# Sheet1.net
KiCad netlist of a schematic drawn in Altium Designer
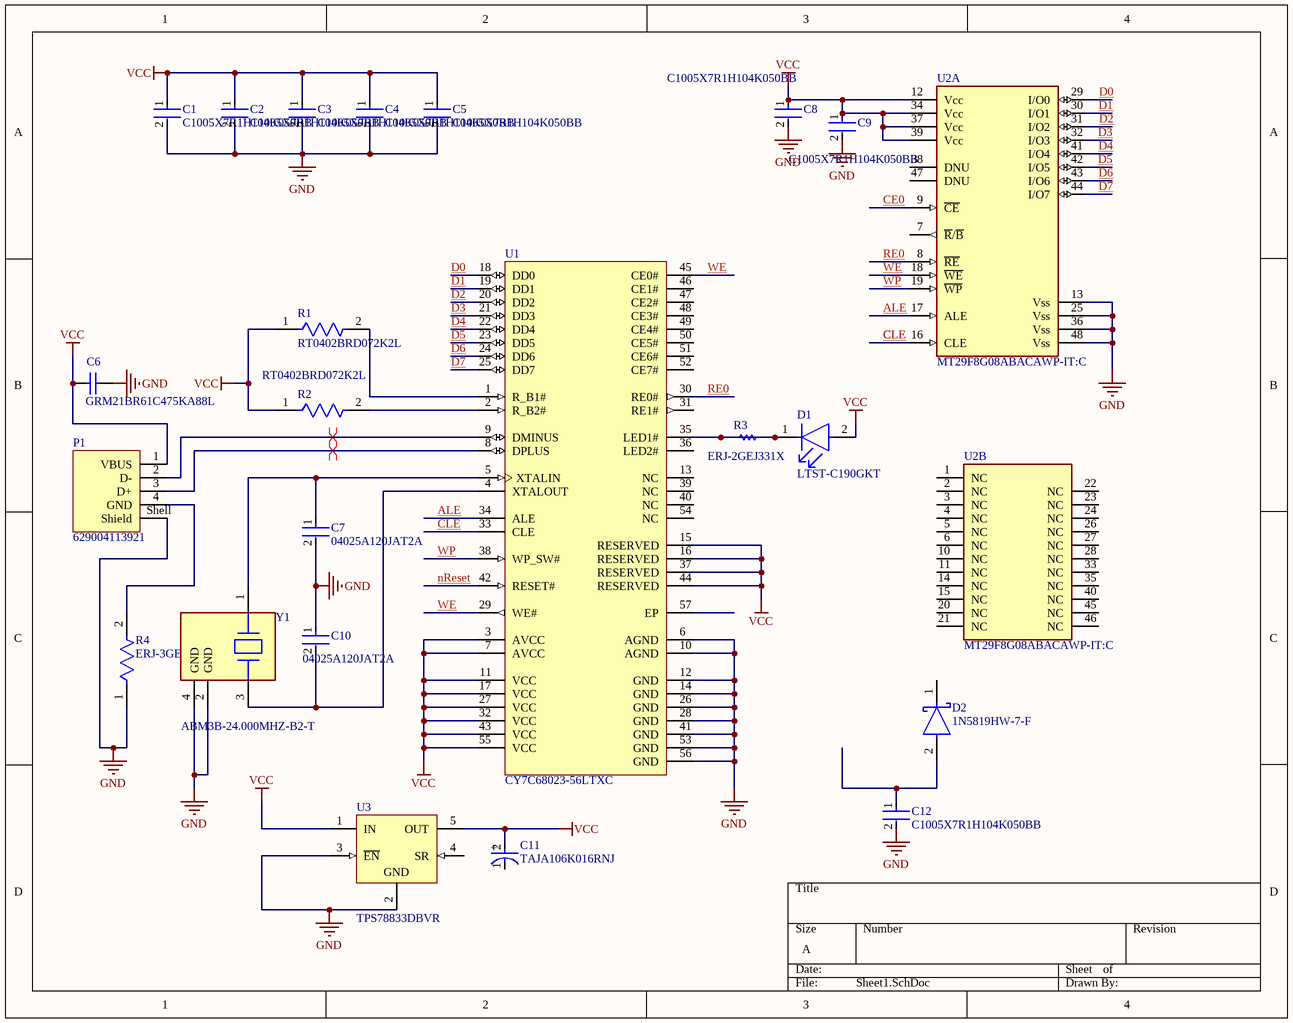
[diagram p0: Sheet1.SchDoc]

(export (version "E")
  (design (tool "Eeschema 10.0.6"))
  (components
    (comp (ref "C1")
      (value "C1005X7R1H104K050BB")
      (footprint "FP-C1005-050-0_05-IPC_C")
      (description "Multilayer Ceramic Capacitors 100nF ±10% 50V X7R SMD 0402")
      (fields (field (name "VOLTAGE") "50V") (field (name "TOLERANCE") "10%"))
      (libsource (lib "Altium Content Vault") (part "b4654b650e69147ec39a6b967a45e02"))
    )
    (comp (ref "C2")
      (value "C1005X7R1H104K050BB")
      (footprint "FP-C1005-050-0_05-IPC_C")
      (description "Multilayer Ceramic Capacitors 100nF ±10% 50V X7R SMD 0402")
      (fields (field (name "VOLTAGE") "50V") (field (name "TOLERANCE") "10%"))
      (libsource (lib "Altium Content Vault") (part "b4654b650e69147ec39a6b967a45e02"))
    )
    (comp (ref "C3")
      (value "C1005X7R1H104K050BB")
      (footprint "FP-C1005-050-0_05-IPC_C")
      (description "Multilayer Ceramic Capacitors 100nF ±10% 50V X7R SMD 0402")
      (fields (field (name "VOLTAGE") "50V") (field (name "TOLERANCE") "10%"))
      (libsource (lib "Altium Content Vault") (part "b4654b650e69147ec39a6b967a45e02"))
    )
    (comp (ref "C4")
      (value "C1005X7R1H104K050BB")
      (footprint "FP-C1005-050-0_05-IPC_C")
      (description "Multilayer Ceramic Capacitors 100nF ±10% 50V X7R SMD 0402")
      (fields (field (name "VOLTAGE") "50V") (field (name "TOLERANCE") "10%"))
      (libsource (lib "Altium Content Vault") (part "b4654b650e69147ec39a6b967a45e02"))
    )
    (comp (ref "C5")
      (value "C1005X7R1H104K050BB")
      (footprint "FP-C1005-050-0_05-IPC_C")
      (description "Multilayer Ceramic Capacitors 100nF ±10% 50V X7R SMD 0402")
      (fields (field (name "VOLTAGE") "50V") (field (name "TOLERANCE") "10%"))
      (libsource (lib "Altium Content Vault") (part "b4654b650e69147ec39a6b967a45e02"))
    )
    (comp (ref "C6")
      (value "GRM21BR61C475KA88L")
      (footprint "CAPC2013X135X45LL10T25")
      (description "Chip Capacitor, 4.7 uF, +/- 10%, 16 V, -55 to 85 degC, 0805 (2012 Metric), RoHS, Tape and Reel")
      (fields (field (name "TOLERANCE") "10%"))
      (libsource (lib "Altium Content Vault") (part "CAP-NP-2"))
    )
    (comp (ref "C7")
      (value "04025A120JAT2A")
      (footprint "FP-0402-L_1_0_1-W_0_5_0_1-IPC_B")
      (description "General Purpose Ceramic Capacitor, 0402, 12pF, 5%, C0G, 30ppm/°C, 50V")
      (fields (field (name "VOLTAGE") "50V") (field (name "TOLERANCE") "5%"))
      (libsource (lib "Altium Content Vault") (part "b4654b650e69147ec39a6b967a45e02"))
    )
    (comp (ref "C8")
      (value "C1005X7R1H104K050BB")
      (footprint "FP-C1005-050-0_05-IPC_C")
      (description "Multilayer Ceramic Capacitors 100nF ±10% 50V X7R SMD 0402")
      (fields (field (name "VOLTAGE") "50V") (field (name "TOLERANCE") "10%"))
      (libsource (lib "Altium Content Vault") (part "b4654b650e69147ec39a6b967a45e02"))
    )
    (comp (ref "C9")
      (value "C1005X7R1H104K050BB")
      (footprint "FP-C1005-050-0_05-IPC_C")
      (description "Multilayer Ceramic Capacitors 100nF ±10% 50V X7R SMD 0402")
      (fields (field (name "VOLTAGE") "50V") (field (name "TOLERANCE") "10%"))
      (libsource (lib "Altium Content Vault") (part "b4654b650e69147ec39a6b967a45e02"))
    )
    (comp (ref "C10")
      (value "04025A120JAT2A")
      (footprint "FP-0402-L_1_0_1-W_0_5_0_1-IPC_B")
      (description "General Purpose Ceramic Capacitor, 0402, 12pF, 5%, C0G, 30ppm/°C, 50V")
      (fields (field (name "VOLTAGE") "50V") (field (name "TOLERANCE") "5%"))
      (libsource (lib "Altium Content Vault") (part "b4654b650e69147ec39a6b967a45e02"))
    )
    (comp (ref "C11")
      (value "TAJA106K016RNJ")
      (footprint "FP-TAJA-MFG")
      (description "10uF 16V  ±10% 3Ω 1206  SMD Tantalum Capacitor")
      (fields (field (name "VOLTAGE") "16V") (field (name "TOLERANCE") "10%"))
      (libsource (lib "Altium Content Vault") (part "203bc49f2ac43e59fd269a8c329ed05"))
    )
    (comp (ref "C12")
      (value "C1005X7R1H104K050BB")
      (footprint "FP-C1005-050-0_05-IPC_C")
      (description "Multilayer Ceramic Capacitors 100nF ±10% 50V X7R SMD 0402")
      (fields (field (name "VOLTAGE") "50V") (field (name "TOLERANCE") "10%"))
      (libsource (lib "Altium Content Vault") (part "b4654b650e69147ec39a6b967a45e02"))
    )
    (comp (ref "D1")
      (value "LTST-C190GKT")
      (footprint "FP-LTST-C190GKT-MFG")
      (description "LED GREEN CLEAR CHIP SMD")
      (fields (field (name "VOLTAGE") "2V"))
      (libsource (lib "Altium Content Vault") (part "8706943c75ba83719d021d2fdc84c58"))
    )
    (comp (ref "D2")
      (value "1N5819HW-7-F")
      (footprint "FP-SOD123-IPC_A")
      (description "DIODE SCHOTTKY 40V 1A SOD123")
      (libsource (lib "Altium Content Vault") (part "1d6ec82d83fb6aee721767c19dac4b9"))
    )
    (comp (ref "P1")
      (value "629004113921")
      (footprint "629004113921")
      (libsource (lib "Altium Content Vault") (part "USB 2.0_Type A_Plug_1 Port"))
    )
    (comp (ref "R1")
      (value "RT0402BRD072K2L")
      (footprint "FP-RT0402-MFG")
      (description "RES SMD 2.2K OHM 0.1% 1/16W 0402")
      (fields (field (name "MANUFACTURER") "Yageo") (field (name "TOLERANCE") "0.001"))
      (libsource (lib "Altium Content Vault") (part "1029c3af85768c4190bb7ad29bc67b5"))
    )
    (comp (ref "R2")
      (value "RT0402BRD072K2L")
      (footprint "FP-RT0402-MFG")
      (description "RES SMD 2.2K OHM 0.1% 1/16W 0402")
      (fields (field (name "MANUFACTURER") "Yageo") (field (name "TOLERANCE") "0.001"))
      (libsource (lib "Altium Content Vault") (part "1029c3af85768c4190bb7ad29bc67b5"))
    )
    (comp (ref "R3")
      (value "ERJ-2GEJ331X")
      (footprint "RESC1005X40X25NL05T05")
      (fields (field (name "MANUFACTURER") "Panasonic"))
      (libsource (lib "Altium Content Vault") (part "RES"))
    )
    (comp (ref "R4")
      (value "ERJ-3GEY0R00V")
      (footprint "FP-ERJ-3GEY0R00V-MFG")
      (description "RES SMD 0 OHM JUMPER 1/10W 0603")
      (fields (field (name "TOLERANCE") "5%") (field (name "MANUFACTURER") "Panasonic"))
      (libsource (lib "Altium Content Vault") (part "1029c3af85768c4190bb7ad29bc67b5"))
    )
    (comp (ref "U1")
      (value "CY7C68023-56LTXC")
      (footprint "CYP-LTX56-5200X4500TP_M")
      (fields (field (name "MANUFACTURER") "Cypress"))
      (libsource (lib "Altium Content Vault") (part "CYP-CY7C68023-LTX56"))
    )
    (comp (ref "U2")
      (value "MT29F8G08ABACAWP-IT:C")
      (footprint "FP-WP-IPC_C")
      (description "IC FLASH 8GBIT PARALLEL 48TSOP I")
      (libsource (lib "Altium Content Vault") (part "ae830fc3658e7ec601516aea8518371"))
    )
    (comp (ref "U3")
      (value "TPS78833DBVR")
      (footprint "DBV0005A_M")
      (fields (field (name "MANUFACTURER") "Texas Instruments"))
      (libsource (lib "Altium Content Vault") (part "TI-TPS788XXDBV5"))
    )
    (comp (ref "Y1")
      (value "ABM3B-24.000MHZ-B2-T")
      (footprint "FP-ABM3B-MFG")
      (description "Crystal 24MHz ±20ppm 18pF SMD-4 5mm x 3.2mm")
      (fields (field (name "TOLERANCE") "20ppm"))
      (libsource (lib "Altium Content Vault") (part "48e526d86b7f2615d98721063c72f49"))
    )
  )
  (nets
    (net (code "1") (name "/ALE") (class "Default")
      (node (ref "U1") (pin "34") (pinfunction "ALE_34") (pintype "tri_state"))
      (node (ref "U2") (pin "17") (pinfunction "ALE_17") (pintype "input"))
    )
    (net (code "2") (name "/CE0") (class "Default")
      (node (ref "U2") (pin "9") (pinfunction "~{CE}_9") (pintype "input"))
    )
    (net (code "3") (name "/CLE") (class "Default")
      (node (ref "U1") (pin "33") (pinfunction "CLE_33") (pintype "tri_state"))
      (node (ref "U2") (pin "16") (pinfunction "CLE_16") (pintype "input"))
    )
    (net (code "4") (name "/D0") (class "Default")
      (node (ref "U1") (pin "18") (pinfunction "DD0_18") (pintype "bidirectional"))
      (node (ref "U2") (pin "29") (pinfunction "I/O0_29") (pintype "bidirectional"))
    )
    (net (code "5") (name "/D1") (class "Default")
      (node (ref "U1") (pin "19") (pinfunction "DD1_19") (pintype "bidirectional"))
      (node (ref "U2") (pin "30") (pinfunction "I/O1_30") (pintype "bidirectional"))
    )
    (net (code "6") (name "/D2") (class "Default")
      (node (ref "U1") (pin "20") (pinfunction "DD2_20") (pintype "bidirectional"))
      (node (ref "U2") (pin "31") (pinfunction "I/O2_31") (pintype "bidirectional"))
    )
    (net (code "7") (name "/D3") (class "Default")
      (node (ref "U1") (pin "21") (pinfunction "DD3_21") (pintype "bidirectional"))
      (node (ref "U2") (pin "32") (pinfunction "I/O3_32") (pintype "bidirectional"))
    )
    (net (code "8") (name "/D4") (class "Default")
      (node (ref "U1") (pin "22") (pinfunction "DD4_22") (pintype "bidirectional"))
      (node (ref "U2") (pin "41") (pinfunction "I/O4_41") (pintype "bidirectional"))
    )
    (net (code "9") (name "/D5") (class "Default")
      (node (ref "U1") (pin "23") (pinfunction "DD5_23") (pintype "bidirectional"))
      (node (ref "U2") (pin "42") (pinfunction "I/O5_42") (pintype "bidirectional"))
    )
    (net (code "10") (name "/D6") (class "Default")
      (node (ref "U1") (pin "24") (pinfunction "DD6_24") (pintype "bidirectional"))
      (node (ref "U2") (pin "43") (pinfunction "I/O6_43") (pintype "bidirectional"))
    )
    (net (code "11") (name "/D7") (class "Default")
      (node (ref "U1") (pin "25") (pinfunction "DD7_25") (pintype "bidirectional"))
      (node (ref "U2") (pin "44") (pinfunction "I/O7_44") (pintype "bidirectional"))
    )
    (net (code "12") (name "/RE0") (class "Default")
      (node (ref "U1") (pin "30") (pinfunction "RE0#_30") (pintype "output"))
      (node (ref "U2") (pin "8") (pinfunction "~{RE}_8") (pintype "input"))
    )
    (net (code "13") (name "/WE") (class "Default")
      (node (ref "U1") (pin "29") (pinfunction "WE#_29") (pintype "output"))
      (node (ref "U1") (pin "45") (pinfunction "CE0#_45") (pintype "tri_state"))
      (node (ref "U2") (pin "18") (pinfunction "~{WE}_18") (pintype "input"))
    )
    (net (code "14") (name "/WP") (class "Default")
      (node (ref "U1") (pin "38") (pinfunction "WP_SW#_38") (pintype "input"))
      (node (ref "U2") (pin "19") (pinfunction "~{WP}_19") (pintype "input"))
    )
    (net (code "15") (name "/nReset") (class "Default")
      (node (ref "U1") (pin "42") (pinfunction "RESET#_42") (pintype "input"))
    )
    (net (code "16") (name "GND") (class "Default")
      (node (ref "C1") (pin "2") (pinfunction "2_2") (pintype "passive"))
      (node (ref "C10") (pin "1") (pinfunction "1_1") (pintype "passive"))
      (node (ref "C12") (pin "2") (pinfunction "2_2") (pintype "passive"))
      (node (ref "C2") (pin "2") (pinfunction "2_2") (pintype "passive"))
      (node (ref "C3") (pin "2") (pinfunction "2_2") (pintype "passive"))
      (node (ref "C4") (pin "2") (pinfunction "2_2") (pintype "passive"))
      (node (ref "C5") (pin "2") (pinfunction "2_2") (pintype "passive"))
      (node (ref "C6") (pin "2") (pinfunction "2_2") (pintype "passive"))
      (node (ref "C7") (pin "2") (pinfunction "2_2") (pintype "passive"))
      (node (ref "C8") (pin "2") (pinfunction "2_2") (pintype "passive"))
      (node (ref "C9") (pin "2") (pinfunction "2_2") (pintype "passive"))
      (node (ref "P1") (pin "Shell") (pinfunction "Shield_Shell") (pintype "passive"))
      (node (ref "R4") (pin "1") (pinfunction "1_1") (pintype "passive"))
      (node (ref "U1") (pin "10") (pinfunction "AGND_10") (pintype "power_in"))
      (node (ref "U1") (pin "12") (pinfunction "GND_12") (pintype "power_in"))
      (node (ref "U1") (pin "14") (pinfunction "GND_14") (pintype "power_in"))
      (node (ref "U1") (pin "26") (pinfunction "GND_26") (pintype "power_in"))
      (node (ref "U1") (pin "28") (pinfunction "GND_28") (pintype "power_in"))
      (node (ref "U1") (pin "41") (pinfunction "GND_41") (pintype "power_in"))
      (node (ref "U1") (pin "53") (pinfunction "GND_53") (pintype "power_in"))
      (node (ref "U1") (pin "56") (pinfunction "GND_56") (pintype "power_in"))
      (node (ref "U1") (pin "6") (pinfunction "AGND_6") (pintype "power_in"))
      (node (ref "U2") (pin "13") (pinfunction "Vss_13") (pintype "power_in"))
      (node (ref "U2") (pin "25") (pinfunction "Vss_25") (pintype "power_in"))
      (node (ref "U2") (pin "36") (pinfunction "Vss_36") (pintype "power_in"))
      (node (ref "U2") (pin "48") (pinfunction "Vss_48") (pintype "power_in"))
      (node (ref "U3") (pin "2") (pinfunction "GND_2") (pintype "power_in"))
      (node (ref "U3") (pin "3") (pinfunction "~{EN}_3") (pintype "input"))
      (node (ref "Y1") (pin "2") (pinfunction "GND_2") (pintype "power_in"))
      (node (ref "Y1") (pin "4") (pinfunction "GND_4") (pintype "power_in"))
    )
    (net (code "17") (name "Net-(D1-C)") (class "Default")
      (node (ref "D1") (pin "1") (pinfunction "C_1") (pintype "passive"))
      (node (ref "R3") (pin "1") (pinfunction "1_1") (pintype "passive"))
      (node (ref "R3") (pin "2") (pinfunction "2_2") (pintype "passive"))
      (node (ref "U1") (pin "35") (pinfunction "LED1#_35") (pintype "tri_state"))
    )
    (net (code "18") (name "Net-(D2-A)") (class "Default")
      (node (ref "C12") (pin "1") (pinfunction "1_1") (pintype "passive"))
      (node (ref "D2") (pin "2") (pinfunction "A_2") (pintype "passive"))
    )
    (net (code "19") (name "Net-(P1-D+)") (class "Default")
      (node (ref "P1") (pin "3") (pinfunction "D+_3") (pintype "passive"))
      (node (ref "U1") (pin "8") (pinfunction "DPLUS_8") (pintype "bidirectional"))
    )
    (net (code "20") (name "Net-(P1-D-)") (class "Default")
      (node (ref "P1") (pin "2") (pinfunction "D-_2") (pintype "passive"))
      (node (ref "U1") (pin "9") (pinfunction "DMINUS_9") (pintype "bidirectional"))
    )
    (net (code "21") (name "Net-(P1-GND)") (class "Default")
      (node (ref "P1") (pin "4") (pinfunction "GND_4") (pintype "passive"))
      (node (ref "R4") (pin "2") (pinfunction "2_2") (pintype "passive"))
    )
    (net (code "22") (name "Net-(U1-R_B1#)") (class "Default")
      (node (ref "R1") (pin "2") (pinfunction "2_2") (pintype "passive"))
      (node (ref "U1") (pin "1") (pinfunction "R_B1#_1") (pintype "input"))
    )
    (net (code "23") (name "Net-(U1-R_B2#)") (class "Default")
      (node (ref "R2") (pin "2") (pinfunction "2_2") (pintype "passive"))
      (node (ref "U1") (pin "2") (pinfunction "R_B2#_2") (pintype "input"))
    )
    (net (code "24") (name "Net-(U1-XTALIN)") (class "Default")
      (node (ref "C7") (pin "1") (pinfunction "1_1") (pintype "passive"))
      (node (ref "U1") (pin "5") (pinfunction "XTALIN_5") (pintype "input"))
      (node (ref "Y1") (pin "1") (pinfunction "1_1") (pintype "passive"))
    )
    (net (code "25") (name "Net-(U1-XTALOUT)") (class "Default")
      (node (ref "C10") (pin "2") (pinfunction "2_2") (pintype "passive"))
      (node (ref "U1") (pin "4") (pinfunction "XTALOUT_4") (pintype "passive"))
      (node (ref "Y1") (pin "3") (pinfunction "3_3") (pintype "passive"))
    )
    (net (code "26") (name "VCC") (class "Default")
      (node (ref "C1") (pin "1") (pinfunction "1_1") (pintype "passive"))
      (node (ref "C11") (pin "2") (pinfunction "A_2") (pintype "passive"))
      (node (ref "C2") (pin "1") (pinfunction "1_1") (pintype "passive"))
      (node (ref "C3") (pin "1") (pinfunction "1_1") (pintype "passive"))
      (node (ref "C4") (pin "1") (pinfunction "1_1") (pintype "passive"))
      (node (ref "C5") (pin "1") (pinfunction "1_1") (pintype "passive"))
      (node (ref "C6") (pin "1") (pinfunction "1_1") (pintype "passive"))
      (node (ref "C8") (pin "1") (pinfunction "1_1") (pintype "passive"))
      (node (ref "C9") (pin "1") (pinfunction "1_1") (pintype "passive"))
      (node (ref "D1") (pin "2") (pinfunction "A_2") (pintype "passive"))
      (node (ref "P1") (pin "1") (pinfunction "VBUS_1") (pintype "passive"))
      (node (ref "R1") (pin "1") (pinfunction "1_1") (pintype "passive"))
      (node (ref "R2") (pin "1") (pinfunction "1_1") (pintype "passive"))
      (node (ref "U1") (pin "11") (pinfunction "VCC_11") (pintype "power_in"))
      (node (ref "U1") (pin "15") (pinfunction "RESERVED_15") (pintype "passive"))
      (node (ref "U1") (pin "16") (pinfunction "RESERVED_16") (pintype "passive"))
      (node (ref "U1") (pin "17") (pinfunction "VCC_17") (pintype "power_in"))
      (node (ref "U1") (pin "27") (pinfunction "VCC_27") (pintype "power_in"))
      (node (ref "U1") (pin "3") (pinfunction "AVCC_3") (pintype "power_in"))
      (node (ref "U1") (pin "32") (pinfunction "VCC_32") (pintype "power_in"))
      (node (ref "U1") (pin "37") (pinfunction "RESERVED_37") (pintype "passive"))
      (node (ref "U1") (pin "43") (pinfunction "VCC_43") (pintype "power_in"))
      (node (ref "U1") (pin "44") (pinfunction "RESERVED_44") (pintype "passive"))
      (node (ref "U1") (pin "55") (pinfunction "VCC_55") (pintype "power_in"))
      (node (ref "U1") (pin "7") (pinfunction "AVCC_7") (pintype "power_in"))
      (node (ref "U2") (pin "12") (pinfunction "Vcc_12") (pintype "power_in"))
      (node (ref "U2") (pin "34") (pinfunction "Vcc_34") (pintype "power_in"))
      (node (ref "U2") (pin "37") (pinfunction "Vcc_37") (pintype "passive"))
      (node (ref "U2") (pin "39") (pinfunction "Vcc_39") (pintype "power_in"))
      (node (ref "U3") (pin "1") (pinfunction "IN_1") (pintype "power_in"))
      (node (ref "U3") (pin "5") (pinfunction "OUT_5") (pintype "power_in"))
    )
    (net (code "27") (name "unconnected-(C11-C-Pad1)") (class "Default")
      (node (ref "C11") (pin "1") (pinfunction "C_1") (pintype "passive"))
    )
    (net (code "28") (name "unconnected-(D2-C-Pad1)") (class "Default")
      (node (ref "D2") (pin "1") (pinfunction "C_1") (pintype "passive"))
    )
    (net (code "29") (name "unconnected-(U1-CE1#-Pad46)") (class "Default")
      (node (ref "U1") (pin "46") (pinfunction "CE1#_46") (pintype "tri_state"))
    )
    (net (code "30") (name "unconnected-(U1-CE2#-Pad47)") (class "Default")
      (node (ref "U1") (pin "47") (pinfunction "CE2#_47") (pintype "tri_state"))
    )
    (net (code "31") (name "unconnected-(U1-CE3#-Pad48)") (class "Default")
      (node (ref "U1") (pin "48") (pinfunction "CE3#_48") (pintype "tri_state"))
    )
    (net (code "32") (name "unconnected-(U1-CE4#-Pad49)") (class "Default")
      (node (ref "U1") (pin "49") (pinfunction "CE4#_49") (pintype "tri_state"))
    )
    (net (code "33") (name "unconnected-(U1-CE5#-Pad50)") (class "Default")
      (node (ref "U1") (pin "50") (pinfunction "CE5#_50") (pintype "tri_state"))
    )
    (net (code "34") (name "unconnected-(U1-CE6#-Pad51)") (class "Default")
      (node (ref "U1") (pin "51") (pinfunction "CE6#_51") (pintype "tri_state"))
    )
    (net (code "35") (name "unconnected-(U1-CE7#-Pad52)") (class "Default")
      (node (ref "U1") (pin "52") (pinfunction "CE7#_52") (pintype "tri_state"))
    )
    (net (code "36") (name "unconnected-(U1-EP-Pad57)") (class "Default")
      (node (ref "U1") (pin "57") (pinfunction "EP_57") (pintype "passive"))
    )
    (net (code "37") (name "unconnected-(U1-LED2#-Pad36)") (class "Default")
      (node (ref "U1") (pin "36") (pinfunction "LED2#_36") (pintype "tri_state"))
    )
    (net (code "38") (name "unconnected-(U1-NC-Pad13)") (class "Default")
      (node (ref "U1") (pin "13") (pinfunction "NC_13") (pintype "passive"))
    )
    (net (code "39") (name "unconnected-(U1-NC-Pad39)") (class "Default")
      (node (ref "U1") (pin "39") (pinfunction "NC_39") (pintype "passive"))
    )
    (net (code "40") (name "unconnected-(U1-NC-Pad40)") (class "Default")
      (node (ref "U1") (pin "40") (pinfunction "NC_40") (pintype "passive"))
    )
    (net (code "41") (name "unconnected-(U1-NC-Pad54)") (class "Default")
      (node (ref "U1") (pin "54") (pinfunction "NC_54") (pintype "passive"))
    )
    (net (code "42") (name "unconnected-(U1-RE1#-Pad31)") (class "Default")
      (node (ref "U1") (pin "31") (pinfunction "RE1#_31") (pintype "output"))
    )
    (net (code "43") (name "unconnected-(U2A-DNU-Pad38)") (class "Default")
      (node (ref "U2") (pin "38") (pinfunction "DNU_38") (pintype "passive"))
    )
    (net (code "44") (name "unconnected-(U2A-DNU-Pad47)") (class "Default")
      (node (ref "U2") (pin "47") (pinfunction "DNU_47") (pintype "passive"))
    )
    (net (code "45") (name "unconnected-(U2A-~{R}{slash}~{B}-Pad7)") (class "Default")
      (node (ref "U2") (pin "7") (pinfunction "~{R}/~{B}_7") (pintype "output"))
    )
    (net (code "46") (name "unconnected-(U2B-NC-Pad1)") (class "Default")
      (node (ref "U2") (pin "1") (pinfunction "NC_1") (pintype "passive"))
    )
    (net (code "47") (name "unconnected-(U2B-NC-Pad2)") (class "Default")
      (node (ref "U2") (pin "2") (pinfunction "NC_2") (pintype "passive"))
    )
    (net (code "48") (name "unconnected-(U2B-NC-Pad3)") (class "Default")
      (node (ref "U2") (pin "3") (pinfunction "NC_3") (pintype "passive"))
    )
    (net (code "49") (name "unconnected-(U2B-NC-Pad4)") (class "Default")
      (node (ref "U2") (pin "4") (pinfunction "NC_4") (pintype "passive"))
    )
    (net (code "50") (name "unconnected-(U2B-NC-Pad5)") (class "Default")
      (node (ref "U2") (pin "5") (pinfunction "NC_5") (pintype "passive"))
    )
    (net (code "51") (name "unconnected-(U2B-NC-Pad6)") (class "Default")
      (node (ref "U2") (pin "6") (pinfunction "NC_6") (pintype "passive"))
    )
    (net (code "52") (name "unconnected-(U2B-NC-Pad10)") (class "Default")
      (node (ref "U2") (pin "10") (pinfunction "NC_10") (pintype "passive"))
    )
    (net (code "53") (name "unconnected-(U2B-NC-Pad11)") (class "Default")
      (node (ref "U2") (pin "11") (pinfunction "NC_11") (pintype "passive"))
    )
    (net (code "54") (name "unconnected-(U2B-NC-Pad14)") (class "Default")
      (node (ref "U2") (pin "14") (pinfunction "NC_14") (pintype "passive"))
    )
    (net (code "55") (name "unconnected-(U2B-NC-Pad15)") (class "Default")
      (node (ref "U2") (pin "15") (pinfunction "NC_15") (pintype "passive"))
    )
    (net (code "56") (name "unconnected-(U2B-NC-Pad20)") (class "Default")
      (node (ref "U2") (pin "20") (pinfunction "NC_20") (pintype "passive"))
    )
    (net (code "57") (name "unconnected-(U2B-NC-Pad21)") (class "Default")
      (node (ref "U2") (pin "21") (pinfunction "NC_21") (pintype "passive"))
    )
    (net (code "58") (name "unconnected-(U2B-NC-Pad22)") (class "Default")
      (node (ref "U2") (pin "22") (pinfunction "NC_22") (pintype "passive"))
    )
    (net (code "59") (name "unconnected-(U2B-NC-Pad23)") (class "Default")
      (node (ref "U2") (pin "23") (pinfunction "NC_23") (pintype "passive"))
    )
    (net (code "60") (name "unconnected-(U2B-NC-Pad24)") (class "Default")
      (node (ref "U2") (pin "24") (pinfunction "NC_24") (pintype "passive"))
    )
    (net (code "61") (name "unconnected-(U2B-NC-Pad26)") (class "Default")
      (node (ref "U2") (pin "26") (pinfunction "NC_26") (pintype "passive"))
    )
    (net (code "62") (name "unconnected-(U2B-NC-Pad27)") (class "Default")
      (node (ref "U2") (pin "27") (pinfunction "NC_27") (pintype "passive"))
    )
    (net (code "63") (name "unconnected-(U2B-NC-Pad28)") (class "Default")
      (node (ref "U2") (pin "28") (pinfunction "NC_28") (pintype "passive"))
    )
    (net (code "64") (name "unconnected-(U2B-NC-Pad33)") (class "Default")
      (node (ref "U2") (pin "33") (pinfunction "NC_33") (pintype "passive"))
    )
    (net (code "65") (name "unconnected-(U2B-NC-Pad35)") (class "Default")
      (node (ref "U2") (pin "35") (pinfunction "NC_35") (pintype "passive"))
    )
    (net (code "66") (name "unconnected-(U2B-NC-Pad40)") (class "Default")
      (node (ref "U2") (pin "40") (pinfunction "NC_40") (pintype "passive"))
    )
    (net (code "67") (name "unconnected-(U2B-NC-Pad45)") (class "Default")
      (node (ref "U2") (pin "45") (pinfunction "NC_45") (pintype "passive"))
    )
    (net (code "68") (name "unconnected-(U2B-NC-Pad46)") (class "Default")
      (node (ref "U2") (pin "46") (pinfunction "NC_46") (pintype "passive"))
    )
    (net (code "69") (name "unconnected-(U3-SR-Pad4)") (class "Default")
      (node (ref "U3") (pin "4") (pinfunction "SR_4") (pintype "input"))
    )
  )
)
